# RH_MRF24_Module.net
KiCad netlist of a schematic drawn in EAGLE
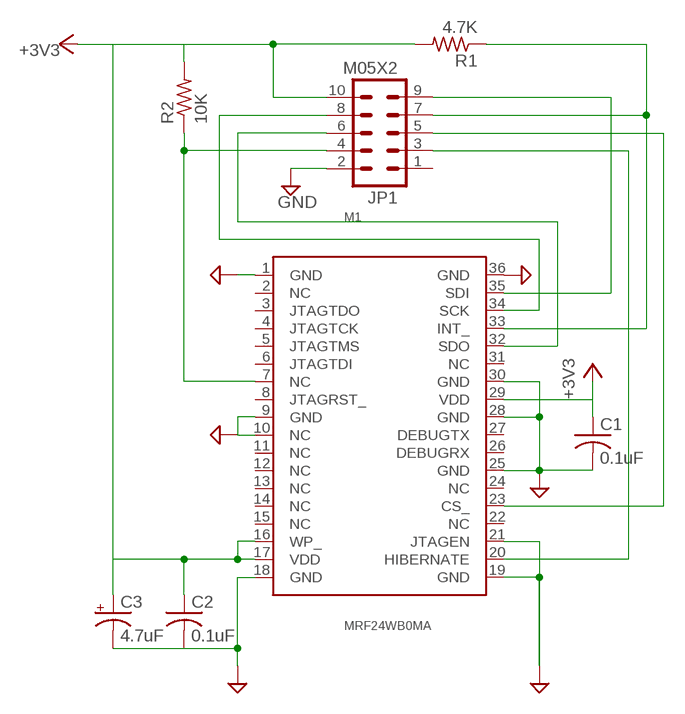
[diagram p0: schematic, sheet 1]

(export (version "E")
  (design (tool "Eeschema 10.0.6"))
  (components
    (comp (ref "C1")
      (value "0.1uF")
      (footprint "eagle-import:C0805")
      (libsource (lib "eagle-import") (part "C-USC0805"))
    )
    (comp (ref "C2")
      (value "0.1uF")
      (footprint "eagle-import:C0805")
      (libsource (lib "eagle-import") (part "C-USC0805"))
    )
    (comp (ref "C3")
      (value "4.7uF")
      (footprint "eagle-import:R_2012-12R")
      (libsource (lib "eagle-import") (part "CPOL-USR/2012-12R"))
    )
    (comp (ref "JP1")
      (value "M05X2")
      (footprint "eagle-import:2X5-RA-HEADER")
      (libsource (lib "eagle-import") (part "M05X2"))
    )
    (comp (ref "M1")
      (value "MRF24WB0MA")
      (footprint "eagle-import:MRF24W")
      (libsource (lib "eagle-import") (part "MR24WB0MA"))
    )
    (comp (ref "R1")
      (value "4.7K")
      (footprint "eagle-import:R0603")
      (libsource (lib "eagle-import") (part "R-US_R0603"))
    )
    (comp (ref "R2")
      (value "10K")
      (footprint "eagle-import:R0603")
      (libsource (lib "eagle-import") (part "R-US_R0603"))
    )
  )
  (nets
    (net (code "1") (name "+3V3") (class "Default")
      (node (ref "C1") (pin "1") (pinfunction "1_1") (pintype "passive"))
      (node (ref "C2") (pin "1") (pinfunction "1_1") (pintype "passive"))
      (node (ref "C3") (pin "+") (pinfunction "+_+") (pintype "passive"))
      (node (ref "JP1") (pin "10") (pinfunction "10_10") (pintype "passive"))
      (node (ref "M1") (pin "16") (pinfunction "WP__16") (pintype "bidirectional"))
      (node (ref "M1") (pin "17") (pinfunction "VDD_17") (pintype "bidirectional"))
      (node (ref "M1") (pin "29") (pinfunction "VDD_29") (pintype "bidirectional"))
      (node (ref "R1") (pin "2") (pinfunction "2_2") (pintype "passive"))
      (node (ref "R2") (pin "2") (pinfunction "2_2") (pintype "passive"))
    )
    (net (code "2") (name "GND") (class "Default")
      (node (ref "C1") (pin "2") (pinfunction "2_2") (pintype "passive"))
      (node (ref "C2") (pin "2") (pinfunction "2_2") (pintype "passive"))
      (node (ref "C3") (pin "-") (pinfunction "-_-") (pintype "passive"))
      (node (ref "JP1") (pin "2") (pinfunction "2_2") (pintype "passive"))
      (node (ref "M1") (pin "1") (pinfunction "GND_1") (pintype "bidirectional"))
      (node (ref "M1") (pin "10") (pinfunction "NC_10") (pintype "bidirectional"))
      (node (ref "M1") (pin "18") (pinfunction "GND_18") (pintype "bidirectional"))
      (node (ref "M1") (pin "19") (pinfunction "GND_19") (pintype "bidirectional"))
      (node (ref "M1") (pin "21") (pinfunction "JTAGEN_21") (pintype "bidirectional"))
      (node (ref "M1") (pin "25") (pinfunction "GND_25") (pintype "bidirectional"))
      (node (ref "M1") (pin "28") (pinfunction "GND_28") (pintype "bidirectional"))
      (node (ref "M1") (pin "30") (pinfunction "GND_30") (pintype "bidirectional"))
      (node (ref "M1") (pin "36") (pinfunction "GND_36") (pintype "bidirectional"))
      (node (ref "M1") (pin "9") (pinfunction "GND_9") (pintype "bidirectional"))
    )
    (net (code "3") (name "Net-(JP1-Pad4)") (class "Default")
      (node (ref "JP1") (pin "4") (pinfunction "4_4") (pintype "passive"))
      (node (ref "M1") (pin "7") (pinfunction "NC_7") (pintype "bidirectional"))
      (node (ref "R2") (pin "1") (pinfunction "1_1") (pintype "passive"))
    )
    (net (code "4") (name "Net-(M1-CS_)") (class "Default")
      (node (ref "JP1") (pin "5") (pinfunction "5_5") (pintype "passive"))
      (node (ref "M1") (pin "23") (pinfunction "CS__23") (pintype "bidirectional"))
    )
    (net (code "5") (name "Net-(M1-HIBERNATE)") (class "Default")
      (node (ref "JP1") (pin "3") (pinfunction "3_3") (pintype "passive"))
      (node (ref "M1") (pin "20") (pinfunction "HIBERNATE_20") (pintype "bidirectional"))
    )
    (net (code "6") (name "Net-(M1-INT_)") (class "Default")
      (node (ref "JP1") (pin "7") (pinfunction "7_7") (pintype "passive"))
      (node (ref "M1") (pin "33") (pinfunction "INT__33") (pintype "bidirectional"))
      (node (ref "R1") (pin "1") (pinfunction "1_1") (pintype "passive"))
    )
    (net (code "7") (name "Net-(M1-SCK)") (class "Default")
      (node (ref "JP1") (pin "8") (pinfunction "8_8") (pintype "passive"))
      (node (ref "M1") (pin "34") (pinfunction "SCK_34") (pintype "bidirectional"))
    )
    (net (code "8") (name "Net-(M1-SDI)") (class "Default")
      (node (ref "JP1") (pin "9") (pinfunction "9_9") (pintype "passive"))
      (node (ref "M1") (pin "35") (pinfunction "SDI_35") (pintype "bidirectional"))
    )
    (net (code "9") (name "Net-(M1-SDO)") (class "Default")
      (node (ref "JP1") (pin "6") (pinfunction "6_6") (pintype "passive"))
      (node (ref "M1") (pin "32") (pinfunction "SDO_32") (pintype "bidirectional"))
    )
    (net (code "10") (name "unconnected-(JP1-Pad1)") (class "Default")
      (node (ref "JP1") (pin "1") (pinfunction "1_1") (pintype "passive"))
    )
    (net (code "11") (name "unconnected-(M1-DEBUGRX-Pad26)") (class "Default")
      (node (ref "M1") (pin "26") (pinfunction "DEBUGRX_26") (pintype "bidirectional"))
    )
    (net (code "12") (name "unconnected-(M1-DEBUGTX-Pad27)") (class "Default")
      (node (ref "M1") (pin "27") (pinfunction "DEBUGTX_27") (pintype "bidirectional"))
    )
    (net (code "13") (name "unconnected-(M1-JTAGRST_-Pad8)") (class "Default")
      (node (ref "M1") (pin "8") (pinfunction "JTAGRST__8") (pintype "bidirectional"))
    )
    (net (code "14") (name "unconnected-(M1-JTAGTCK-Pad4)") (class "Default")
      (node (ref "M1") (pin "4") (pinfunction "JTAGTCK_4") (pintype "bidirectional"))
    )
    (net (code "15") (name "unconnected-(M1-JTAGTDI-Pad6)") (class "Default")
      (node (ref "M1") (pin "6") (pinfunction "JTAGTDI_6") (pintype "bidirectional"))
    )
    (net (code "16") (name "unconnected-(M1-JTAGTDO-Pad3)") (class "Default")
      (node (ref "M1") (pin "3") (pinfunction "JTAGTDO_3") (pintype "bidirectional"))
    )
    (net (code "17") (name "unconnected-(M1-JTAGTMS-Pad5)") (class "Default")
      (node (ref "M1") (pin "5") (pinfunction "JTAGTMS_5") (pintype "bidirectional"))
    )
    (net (code "18") (name "unconnected-(M1-NC-Pad2)") (class "Default")
      (node (ref "M1") (pin "2") (pinfunction "NC_2") (pintype "bidirectional"))
    )
    (net (code "19") (name "unconnected-(M1-NC-Pad11)") (class "Default")
      (node (ref "M1") (pin "11") (pinfunction "NC_11") (pintype "bidirectional"))
    )
    (net (code "20") (name "unconnected-(M1-NC-Pad12)") (class "Default")
      (node (ref "M1") (pin "12") (pinfunction "NC_12") (pintype "bidirectional"))
    )
    (net (code "21") (name "unconnected-(M1-NC-Pad13)") (class "Default")
      (node (ref "M1") (pin "13") (pinfunction "NC_13") (pintype "bidirectional"))
    )
    (net (code "22") (name "unconnected-(M1-NC-Pad14)") (class "Default")
      (node (ref "M1") (pin "14") (pinfunction "NC_14") (pintype "bidirectional"))
    )
    (net (code "23") (name "unconnected-(M1-NC-Pad15)") (class "Default")
      (node (ref "M1") (pin "15") (pinfunction "NC_15") (pintype "bidirectional"))
    )
    (net (code "24") (name "unconnected-(M1-NC-Pad22)") (class "Default")
      (node (ref "M1") (pin "22") (pinfunction "NC_22") (pintype "bidirectional"))
    )
    (net (code "25") (name "unconnected-(M1-NC-Pad24)") (class "Default")
      (node (ref "M1") (pin "24") (pinfunction "NC_24") (pintype "bidirectional"))
    )
    (net (code "26") (name "unconnected-(M1-NC-Pad31)") (class "Default")
      (node (ref "M1") (pin "31") (pinfunction "NC_31") (pintype "bidirectional"))
    )
  )
)
